# Sheet3.net
KiCad netlist of a schematic drawn in Altium Designer
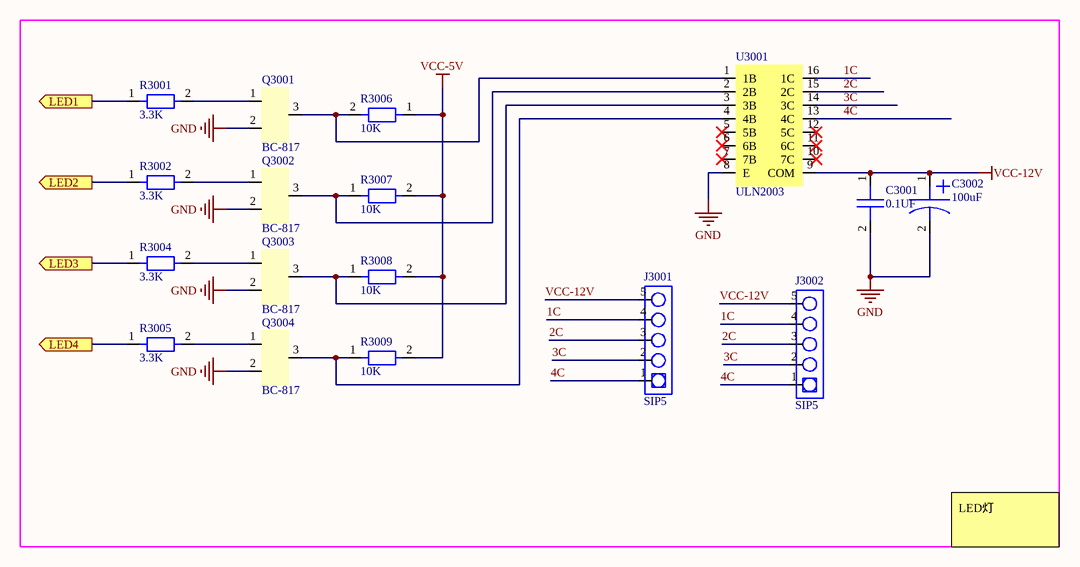
[diagram p0: Sheet3.SchDoc]

(export (version "E")
  (design (tool "Eeschema 10.0.6"))
  (components
    (comp (ref "C3001") (value "0.1UF") (footprint "0603") (libsource (lib "Schlib1") (part "C")))
    (comp (ref "C3002") (value "100uF") (footprint "7343") (libsource (lib "Schlib1") (part "极性电容")))
    (comp (ref "J3001") (value "SIP5") (footprint "SIP5") (libsource (lib "Schlib1") (part "SIP5")))
    (comp (ref "J3002") (value "SIP5") (footprint "SIP5") (libsource (lib "Schlib1") (part "SIP5")))
    (comp (ref "Q3001") (value "BC-817") (footprint "S9013") (libsource (lib "Schlib1") (part "BC-817")))
    (comp (ref "Q3002") (value "BC-817") (footprint "S9013") (libsource (lib "Schlib1") (part "BC-817")))
    (comp (ref "Q3003") (value "BC-817") (footprint "S9013") (libsource (lib "Schlib1") (part "BC-817")))
    (comp (ref "Q3004") (value "BC-817") (footprint "S9013") (libsource (lib "Schlib1") (part "BC-817")))
    (comp (ref "R3001") (value "3.3K") (footprint "0603") (libsource (lib "Schlib1") (part "R")))
    (comp (ref "R3002") (value "3.3K") (footprint "0603") (libsource (lib "Schlib1") (part "R")))
    (comp (ref "R3004") (value "3.3K") (footprint "0603") (libsource (lib "Schlib1") (part "R")))
    (comp (ref "R3005") (value "3.3K") (footprint "0603") (libsource (lib "Schlib1") (part "R")))
    (comp (ref "R3006") (value "10K") (footprint "0603") (libsource (lib "Schlib1") (part "R")))
    (comp (ref "R3007") (value "10K") (footprint "0603") (libsource (lib "Schlib1") (part "R")))
    (comp (ref "R3008") (value "10K") (footprint "0603") (libsource (lib "Schlib1") (part "R")))
    (comp (ref "R3009") (value "10K") (footprint "0603") (libsource (lib "Schlib1") (part "R")))
    (comp (ref "U3001") (value "ULN2003") (footprint "ULN2003A") (libsource (lib "Schlib1") (part "ULN2003")))
  )
  (nets
    (net (code "1") (name "/1C") (class "Default")
      (node (ref "J3001") (pin "4") (pintype "passive"))
      (node (ref "J3002") (pin "4") (pintype "passive"))
      (node (ref "U3001") (pin "16") (pinfunction "1C_16") (pintype "passive"))
    )
    (net (code "2") (name "/2C") (class "Default")
      (node (ref "J3001") (pin "3") (pintype "passive"))
      (node (ref "J3002") (pin "3") (pintype "passive"))
      (node (ref "U3001") (pin "15") (pinfunction "2C_15") (pintype "passive"))
    )
    (net (code "3") (name "/3C") (class "Default")
      (node (ref "J3001") (pin "2") (pintype "passive"))
      (node (ref "J3002") (pin "2") (pintype "passive"))
      (node (ref "U3001") (pin "14") (pinfunction "3C_14") (pintype "passive"))
    )
    (net (code "4") (name "/4C") (class "Default")
      (node (ref "J3001") (pin "1") (pintype "passive"))
      (node (ref "J3002") (pin "1") (pintype "passive"))
      (node (ref "U3001") (pin "13") (pinfunction "4C_13") (pintype "passive"))
    )
    (net (code "5") (name "/LED1") (class "Default") (node (ref "R3001") (pin "1") (pintype "passive")))
    (net (code "6") (name "/LED2") (class "Default") (node (ref "R3002") (pin "1") (pintype "passive")))
    (net (code "7") (name "/LED3") (class "Default") (node (ref "R3004") (pin "1") (pintype "passive")))
    (net (code "8") (name "/LED4") (class "Default") (node (ref "R3005") (pin "1") (pintype "passive")))
    (net (code "9") (name "GND") (class "Default")
      (node (ref "C3001") (pin "2") (pintype "passive"))
      (node (ref "C3002") (pin "2") (pintype "passive"))
      (node (ref "Q3001") (pin "2") (pintype "passive"))
      (node (ref "Q3002") (pin "2") (pintype "passive"))
      (node (ref "Q3003") (pin "2") (pintype "passive"))
      (node (ref "Q3004") (pin "2") (pintype "passive"))
      (node (ref "U3001") (pin "8") (pinfunction "E_8") (pintype "passive"))
    )
    (net (code "10") (name "Net-(Q3001-Pad1)") (class "Default")
      (node (ref "Q3001") (pin "1") (pintype "passive"))
      (node (ref "R3001") (pin "2") (pintype "passive"))
    )
    (net (code "11") (name "Net-(Q3002-Pad1)") (class "Default")
      (node (ref "Q3002") (pin "1") (pintype "passive"))
      (node (ref "R3002") (pin "2") (pintype "passive"))
    )
    (net (code "12") (name "Net-(Q3003-Pad1)") (class "Default")
      (node (ref "Q3003") (pin "1") (pintype "passive"))
      (node (ref "R3004") (pin "2") (pintype "passive"))
    )
    (net (code "13") (name "Net-(Q3004-Pad1)") (class "Default")
      (node (ref "Q3004") (pin "1") (pintype "passive"))
      (node (ref "R3005") (pin "2") (pintype "passive"))
    )
    (net (code "14") (name "Net-(U3001-1B)") (class "Default")
      (node (ref "Q3001") (pin "3") (pintype "passive"))
      (node (ref "R3006") (pin "2") (pintype "passive"))
      (node (ref "U3001") (pin "1") (pinfunction "1B_1") (pintype "passive"))
    )
    (net (code "15") (name "Net-(U3001-2B)") (class "Default")
      (node (ref "Q3002") (pin "3") (pintype "passive"))
      (node (ref "R3007") (pin "1") (pintype "passive"))
      (node (ref "U3001") (pin "2") (pinfunction "2B_2") (pintype "passive"))
    )
    (net (code "16") (name "Net-(U3001-3B)") (class "Default")
      (node (ref "Q3003") (pin "3") (pintype "passive"))
      (node (ref "R3008") (pin "1") (pintype "passive"))
      (node (ref "U3001") (pin "3") (pinfunction "3B_3") (pintype "passive"))
    )
    (net (code "17") (name "Net-(U3001-4B)") (class "Default")
      (node (ref "Q3004") (pin "3") (pintype "passive"))
      (node (ref "R3009") (pin "1") (pintype "passive"))
      (node (ref "U3001") (pin "4") (pinfunction "4B_4") (pintype "passive"))
    )
    (net (code "18") (name "VCC-5V") (class "Default")
      (node (ref "R3006") (pin "1") (pintype "passive"))
      (node (ref "R3007") (pin "2") (pintype "passive"))
      (node (ref "R3008") (pin "2") (pintype "passive"))
      (node (ref "R3009") (pin "2") (pintype "passive"))
    )
    (net (code "19") (name "VCC-12V") (class "Default")
      (node (ref "C3001") (pin "1") (pintype "passive"))
      (node (ref "C3002") (pin "1") (pintype "passive"))
      (node (ref "J3001") (pin "5") (pintype "passive"))
      (node (ref "J3002") (pin "5") (pintype "passive"))
      (node (ref "U3001") (pin "9") (pinfunction "COM_9") (pintype "passive"))
    )
    (net (code "20") (name "unconnected-(U3001-5B-Pad5)") (class "Default")
      (node (ref "U3001") (pin "5") (pinfunction "5B_5") (pintype "passive+no_connect"))
    )
    (net (code "21") (name "unconnected-(U3001-5C-Pad12)") (class "Default")
      (node (ref "U3001") (pin "12") (pinfunction "5C_12") (pintype "passive+no_connect"))
    )
    (net (code "22") (name "unconnected-(U3001-6B-Pad6)") (class "Default")
      (node (ref "U3001") (pin "6") (pinfunction "6B_6") (pintype "passive+no_connect"))
    )
    (net (code "23") (name "unconnected-(U3001-6C-Pad11)") (class "Default")
      (node (ref "U3001") (pin "11") (pinfunction "6C_11") (pintype "passive+no_connect"))
    )
    (net (code "24") (name "unconnected-(U3001-7B-Pad7)") (class "Default")
      (node (ref "U3001") (pin "7") (pinfunction "7B_7") (pintype "passive+no_connect"))
    )
    (net (code "25") (name "unconnected-(U3001-7C-Pad10)") (class "Default")
      (node (ref "U3001") (pin "10") (pinfunction "7C_10") (pintype "passive+no_connect"))
    )
  )
)
